# sm7_redraw.net
KiCad netlist of a schematic drawn in EAGLE
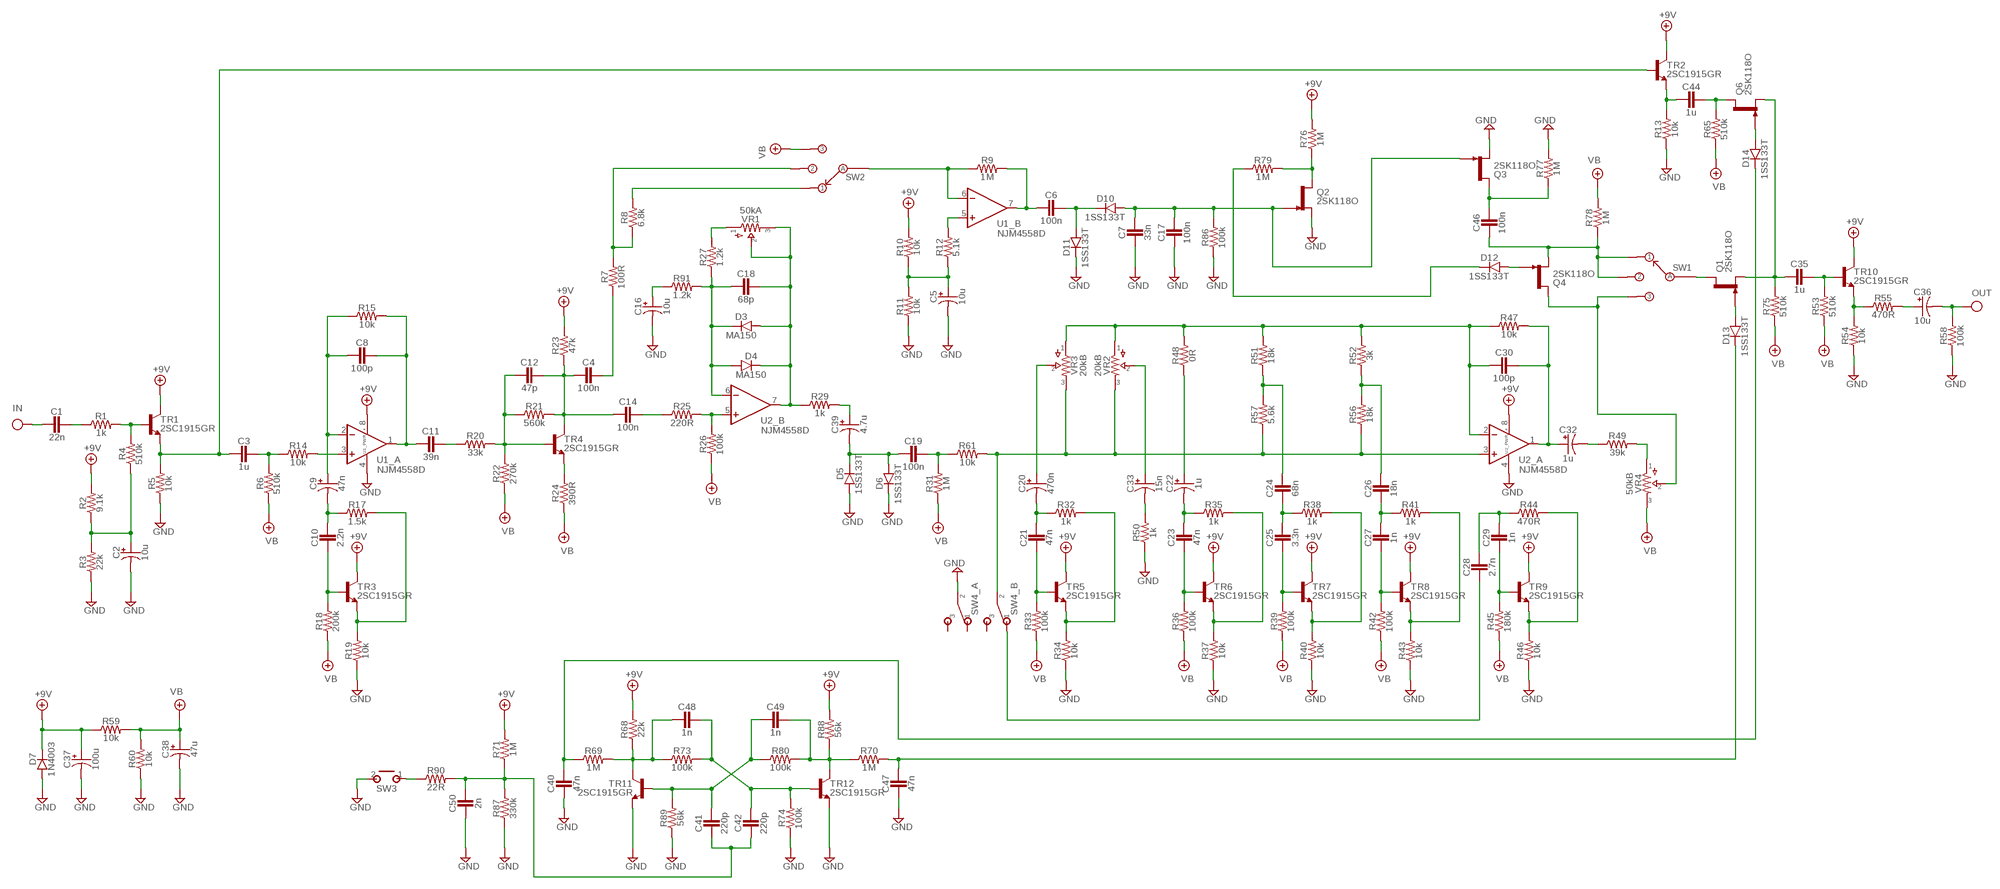
[diagram p0: schematic, sheet 1]

(export (version "E")
  (design (tool "Eeschema 10.0.6"))
  (components
    (comp (ref "C1")
      (value "22n")
      (footprint "eagle-import:BOX_SMALL")
      (libsource (lib "eagle-import") (part "CER/FILMBOX.1"))
    )
    (comp (ref "C2")
      (value "10u")
      (footprint "eagle-import:040_020")
      (libsource (lib "eagle-import") (part "0400"))
    )
    (comp (ref "C3")
      (value "1u")
      (footprint "eagle-import:BOX_SMALL")
      (libsource (lib "eagle-import") (part "CER/FILMBOX.1"))
    )
    (comp (ref "C4")
      (value "100n")
      (footprint "eagle-import:BOX_SMALL")
      (libsource (lib "eagle-import") (part "CER/FILMBOX.1"))
    )
    (comp (ref "C5")
      (value "10u")
      (footprint "eagle-import:040_020")
      (libsource (lib "eagle-import") (part "0400"))
    )
    (comp (ref "C6")
      (value "100n")
      (footprint "eagle-import:BOX_SMALL")
      (libsource (lib "eagle-import") (part "CER/FILMBOX.1"))
    )
    (comp (ref "C7")
      (value "33n")
      (footprint "eagle-import:BOX_SMALL")
      (libsource (lib "eagle-import") (part "CER/FILMBOX.1"))
    )
    (comp (ref "C8")
      (value "100p")
      (footprint "eagle-import:BOX_SMALL")
      (libsource (lib "eagle-import") (part "CER/FILMBOX.1"))
    )
    (comp (ref "C9")
      (value "47n")
      (footprint "eagle-import:040_020")
      (libsource (lib "eagle-import") (part "0400"))
    )
    (comp (ref "C10")
      (value "2.2n")
      (footprint "eagle-import:BOX_SMALL")
      (libsource (lib "eagle-import") (part "CER/FILMBOX.1"))
    )
    (comp (ref "C11")
      (value "39n")
      (footprint "eagle-import:BOX_SMALL")
      (libsource (lib "eagle-import") (part "CER/FILMBOX.1"))
    )
    (comp (ref "C12")
      (value "47p")
      (footprint "eagle-import:BOX_SMALL")
      (libsource (lib "eagle-import") (part "CER/FILMBOX.1"))
    )
    (comp (ref "C14")
      (value "100n")
      (footprint "eagle-import:BOX_SMALL")
      (libsource (lib "eagle-import") (part "CER/FILMBOX.1"))
    )
    (comp (ref "C16")
      (value "10u")
      (footprint "eagle-import:040_020")
      (libsource (lib "eagle-import") (part "0400"))
    )
    (comp (ref "C17")
      (value "100n")
      (footprint "eagle-import:BOX_SMALL")
      (libsource (lib "eagle-import") (part "CER/FILMBOX.1"))
    )
    (comp (ref "C18")
      (value "68p")
      (footprint "eagle-import:BOX_SMALL")
      (libsource (lib "eagle-import") (part "CER/FILMBOX.1"))
    )
    (comp (ref "C19")
      (value "100n")
      (footprint "eagle-import:BOX_SMALL")
      (libsource (lib "eagle-import") (part "CER/FILMBOX.1"))
    )
    (comp (ref "C20")
      (value "470n")
      (footprint "eagle-import:040_020")
      (libsource (lib "eagle-import") (part "0400"))
    )
    (comp (ref "C21")
      (value "47n")
      (footprint "eagle-import:BOX_SMALL")
      (libsource (lib "eagle-import") (part "CER/FILMBOX.1"))
    )
    (comp (ref "C22")
      (value "1u")
      (footprint "eagle-import:040_020")
      (libsource (lib "eagle-import") (part "0400"))
    )
    (comp (ref "C23")
      (value "47n")
      (footprint "eagle-import:BOX_SMALL")
      (libsource (lib "eagle-import") (part "CER/FILMBOX.1"))
    )
    (comp (ref "C24")
      (value "68n")
      (footprint "eagle-import:BOX_SMALL")
      (libsource (lib "eagle-import") (part "CER/FILMBOX.1"))
    )
    (comp (ref "C25")
      (value "3.3n")
      (footprint "eagle-import:BOX_SMALL")
      (libsource (lib "eagle-import") (part "CER/FILMBOX.1"))
    )
    (comp (ref "C26")
      (value "18n")
      (footprint "eagle-import:BOX_SMALL")
      (libsource (lib "eagle-import") (part "CER/FILMBOX.1"))
    )
    (comp (ref "C27")
      (value "1n")
      (footprint "eagle-import:BOX_SMALL")
      (libsource (lib "eagle-import") (part "CER/FILMBOX.1"))
    )
    (comp (ref "C28")
      (value "2.7n")
      (footprint "eagle-import:BOX_SMALL")
      (libsource (lib "eagle-import") (part "CER/FILMBOX.1"))
    )
    (comp (ref "C29")
      (value "1n")
      (footprint "eagle-import:BOX_SMALL")
      (libsource (lib "eagle-import") (part "CER/FILMBOX.1"))
    )
    (comp (ref "C30")
      (value "100p")
      (footprint "eagle-import:BOX_SMALL")
      (libsource (lib "eagle-import") (part "CER/FILMBOX.1"))
    )
    (comp (ref "C32")
      (value "1u")
      (footprint "eagle-import:040_020")
      (libsource (lib "eagle-import") (part "0400"))
    )
    (comp (ref "C33")
      (value "15n")
      (footprint "eagle-import:040_020")
      (libsource (lib "eagle-import") (part "0400"))
    )
    (comp (ref "C35")
      (value "1u")
      (footprint "eagle-import:BOX_SMALL")
      (libsource (lib "eagle-import") (part "CER/FILMBOX.1"))
    )
    (comp (ref "C36")
      (value "10u")
      (footprint "eagle-import:040_020")
      (libsource (lib "eagle-import") (part "0400"))
    )
    (comp (ref "C37")
      (value "100u")
      (footprint "eagle-import:040_020")
      (libsource (lib "eagle-import") (part "0400"))
    )
    (comp (ref "C38")
      (value "47u")
      (footprint "eagle-import:040_020")
      (libsource (lib "eagle-import") (part "0400"))
    )
    (comp (ref "C39")
      (value "4.7u")
      (footprint "eagle-import:040_020")
      (libsource (lib "eagle-import") (part "0400"))
    )
    (comp (ref "C40")
      (value "47n")
      (footprint "eagle-import:BOX_SMALL")
      (libsource (lib "eagle-import") (part "CER/FILMBOX.1"))
    )
    (comp (ref "C41")
      (value "220p")
      (footprint "eagle-import:BOX_SMALL")
      (libsource (lib "eagle-import") (part "CER/FILMBOX.1"))
    )
    (comp (ref "C42")
      (value "220p")
      (footprint "eagle-import:BOX_SMALL")
      (libsource (lib "eagle-import") (part "CER/FILMBOX.1"))
    )
    (comp (ref "C44")
      (value "1u")
      (footprint "eagle-import:BOX_SMALL")
      (libsource (lib "eagle-import") (part "CER/FILMBOX.1"))
    )
    (comp (ref "C46")
      (value "100n")
      (footprint "eagle-import:BOX_SMALL")
      (libsource (lib "eagle-import") (part "CER/FILMBOX.1"))
    )
    (comp (ref "C47")
      (value "47n")
      (footprint "eagle-import:BOX_SMALL")
      (libsource (lib "eagle-import") (part "CER/FILMBOX.1"))
    )
    (comp (ref "C48")
      (value "1n")
      (footprint "eagle-import:BOX_SMALL")
      (libsource (lib "eagle-import") (part "CER/FILMBOX.1"))
    )
    (comp (ref "C49")
      (value "1n")
      (footprint "eagle-import:BOX_SMALL")
      (libsource (lib "eagle-import") (part "CER/FILMBOX.1"))
    )
    (comp (ref "C50")
      (value "2n")
      (footprint "eagle-import:BOX_SMALL")
      (libsource (lib "eagle-import") (part "CER/FILMBOX.1"))
    )
    (comp (ref "D3")
      (value "MA150")
      (footprint "eagle-import:DO41-2")
      (libsource (lib "eagle-import") (part "DO41.2"))
    )
    (comp (ref "D4")
      (value "MA150")
      (footprint "eagle-import:DO41-2")
      (libsource (lib "eagle-import") (part "DO41.2"))
    )
    (comp (ref "D5")
      (value "1SS133T")
      (footprint "eagle-import:DO41-2")
      (libsource (lib "eagle-import") (part "DO41.2"))
    )
    (comp (ref "D6")
      (value "1SS133T")
      (footprint "eagle-import:DO41-2")
      (libsource (lib "eagle-import") (part "DO41.2"))
    )
    (comp (ref "D7")
      (value "1N4003")
      (footprint "eagle-import:DO41-2")
      (libsource (lib "eagle-import") (part "DO41.2"))
    )
    (comp (ref "D10")
      (value "1SS133T")
      (footprint "eagle-import:DO41-2")
      (libsource (lib "eagle-import") (part "DO41.2"))
    )
    (comp (ref "D11")
      (value "1SS133T")
      (footprint "eagle-import:DO41-2")
      (libsource (lib "eagle-import") (part "DO41.2"))
    )
    (comp (ref "D12")
      (value "1SS133T")
      (footprint "eagle-import:DO41-2")
      (libsource (lib "eagle-import") (part "DO41.2"))
    )
    (comp (ref "D13")
      (value "1SS133T")
      (footprint "eagle-import:DO41-2")
      (libsource (lib "eagle-import") (part "DO41.2"))
    )
    (comp (ref "D14")
      (value "1SS133T")
      (footprint "eagle-import:DO41-2")
      (libsource (lib "eagle-import") (part "DO41.2"))
    )
    (comp (ref "Q1")
      (value "2SK118O")
      (footprint "eagle-import:TO92-")
      (libsource (lib "eagle-import") (part "2N5457"))
    )
    (comp (ref "Q2")
      (value "2SK118O")
      (footprint "eagle-import:TO92-")
      (libsource (lib "eagle-import") (part "2N5457"))
    )
    (comp (ref "Q3")
      (value "2SK118O")
      (footprint "eagle-import:TO92-")
      (libsource (lib "eagle-import") (part "2N5457"))
    )
    (comp (ref "Q4")
      (value "2SK118O")
      (footprint "eagle-import:TO92-")
      (libsource (lib "eagle-import") (part "2N5457"))
    )
    (comp (ref "Q6")
      (value "2SK118O")
      (footprint "eagle-import:TO92-")
      (libsource (lib "eagle-import") (part "2N5457"))
    )
    (comp (ref "R1")
      (value "1k")
      (footprint "eagle-import:R0207_3")
      (libsource (lib "eagle-import") (part "R_.3B"))
    )
    (comp (ref "R2")
      (value "9.1k")
      (footprint "eagle-import:R0207_3")
      (libsource (lib "eagle-import") (part "R_.3B"))
    )
    (comp (ref "R3")
      (value "22k")
      (footprint "eagle-import:R0207_3")
      (libsource (lib "eagle-import") (part "R_.3B"))
    )
    (comp (ref "R4")
      (value "510k")
      (footprint "eagle-import:R0207_3")
      (libsource (lib "eagle-import") (part "R_.3B"))
    )
    (comp (ref "R5")
      (value "10k")
      (footprint "eagle-import:R0207_3")
      (libsource (lib "eagle-import") (part "R_.3B"))
    )
    (comp (ref "R6")
      (value "510k")
      (footprint "eagle-import:R0207_3")
      (libsource (lib "eagle-import") (part "R_.3B"))
    )
    (comp (ref "R7")
      (value "100R")
      (footprint "eagle-import:R0207_3")
      (libsource (lib "eagle-import") (part "R_.3B"))
    )
    (comp (ref "R8")
      (value "6.8k")
      (footprint "eagle-import:R0207_3")
      (libsource (lib "eagle-import") (part "R_.3B"))
    )
    (comp (ref "R9")
      (value "1M")
      (footprint "eagle-import:R0207_3")
      (libsource (lib "eagle-import") (part "R_.3B"))
    )
    (comp (ref "R10")
      (value "10k")
      (footprint "eagle-import:R0207_3")
      (libsource (lib "eagle-import") (part "R_.3B"))
    )
    (comp (ref "R11")
      (value "10k")
      (footprint "eagle-import:R0207_3")
      (libsource (lib "eagle-import") (part "R_.3B"))
    )
    (comp (ref "R12")
      (value "5.1k")
      (footprint "eagle-import:R0207_3")
      (libsource (lib "eagle-import") (part "R_.3B"))
    )
    (comp (ref "R13")
      (value "10k")
      (footprint "eagle-import:R0207_3")
      (libsource (lib "eagle-import") (part "R_.3B"))
    )
    (comp (ref "R14")
      (value "10k")
      (footprint "eagle-import:R0207_3")
      (libsource (lib "eagle-import") (part "R_.3B"))
    )
    (comp (ref "R15")
      (value "10k")
      (footprint "eagle-import:R0207_3")
      (libsource (lib "eagle-import") (part "R_.3B"))
    )
    (comp (ref "R17")
      (value "1.5k")
      (footprint "eagle-import:R0207_3")
      (libsource (lib "eagle-import") (part "R_.3B"))
    )
    (comp (ref "R18")
      (value "200k")
      (footprint "eagle-import:R0207_3")
      (libsource (lib "eagle-import") (part "R_.3B"))
    )
    (comp (ref "R19")
      (value "10k")
      (footprint "eagle-import:R0207_3")
      (libsource (lib "eagle-import") (part "R_.3B"))
    )
    (comp (ref "R20")
      (value "33k")
      (footprint "eagle-import:R0207_3")
      (libsource (lib "eagle-import") (part "R_.3B"))
    )
    (comp (ref "R21")
      (value "560k")
      (footprint "eagle-import:R0207_3")
      (libsource (lib "eagle-import") (part "R_.3B"))
    )
    (comp (ref "R22")
      (value "270k")
      (footprint "eagle-import:R0207_3")
      (libsource (lib "eagle-import") (part "R_.3B"))
    )
    (comp (ref "R23")
      (value "47k")
      (footprint "eagle-import:R0207_3")
      (libsource (lib "eagle-import") (part "R_.3B"))
    )
    (comp (ref "R24")
      (value "390R")
      (footprint "eagle-import:R0207_3")
      (libsource (lib "eagle-import") (part "R_.3B"))
    )
    (comp (ref "R25")
      (value "220R")
      (footprint "eagle-import:R0207_3")
      (libsource (lib "eagle-import") (part "R_.3B"))
    )
    (comp (ref "R26")
      (value "100k")
      (footprint "eagle-import:R0207_3")
      (libsource (lib "eagle-import") (part "R_.3B"))
    )
    (comp (ref "R27")
      (value "1.2k")
      (footprint "eagle-import:R0207_3")
      (libsource (lib "eagle-import") (part "R_.3B"))
    )
    (comp (ref "R29")
      (value "1k")
      (footprint "eagle-import:R0207_3")
      (libsource (lib "eagle-import") (part "R_.3B"))
    )
    (comp (ref "R31")
      (value "1M")
      (footprint "eagle-import:R0207_3")
      (libsource (lib "eagle-import") (part "R_.3B"))
    )
    (comp (ref "R32")
      (value "1k")
      (footprint "eagle-import:R0207_3")
      (libsource (lib "eagle-import") (part "R_.3B"))
    )
    (comp (ref "R33")
      (value "100k")
      (footprint "eagle-import:R0207_3")
      (libsource (lib "eagle-import") (part "R_.3B"))
    )
    (comp (ref "R34")
      (value "10k")
      (footprint "eagle-import:R0207_3")
      (libsource (lib "eagle-import") (part "R_.3B"))
    )
    (comp (ref "R35")
      (value "1k")
      (footprint "eagle-import:R0207_3")
      (libsource (lib "eagle-import") (part "R_.3B"))
    )
    (comp (ref "R36")
      (value "100k")
      (footprint "eagle-import:R0207_3")
      (libsource (lib "eagle-import") (part "R_.3B"))
    )
    (comp (ref "R37")
      (value "10k")
      (footprint "eagle-import:R0207_3")
      (libsource (lib "eagle-import") (part "R_.3B"))
    )
    (comp (ref "R38")
      (value "1k")
      (footprint "eagle-import:R0207_3")
      (libsource (lib "eagle-import") (part "R_.3B"))
    )
    (comp (ref "R39")
      (value "100k")
      (footprint "eagle-import:R0207_3")
      (libsource (lib "eagle-import") (part "R_.3B"))
    )
    (comp (ref "R40")
      (value "10k")
      (footprint "eagle-import:R0207_3")
      (libsource (lib "eagle-import") (part "R_.3B"))
    )
    (comp (ref "R41")
      (value "1k")
      (footprint "eagle-import:R0207_3")
      (libsource (lib "eagle-import") (part "R_.3B"))
    )
    (comp (ref "R42")
      (value "100k")
      (footprint "eagle-import:R0207_3")
      (libsource (lib "eagle-import") (part "R_.3B"))
    )
    (comp (ref "R43")
      (value "10k")
      (footprint "eagle-import:R0207_3")
      (libsource (lib "eagle-import") (part "R_.3B"))
    )
    (comp (ref "R44")
      (value "470R")
      (footprint "eagle-import:R0207_3")
      (libsource (lib "eagle-import") (part "R_.3B"))
    )
    (comp (ref "R45")
      (value "180k")
      (footprint "eagle-import:R0207_3")
      (libsource (lib "eagle-import") (part "R_.3B"))
    )
    (comp (ref "R46")
      (value "10k")
      (footprint "eagle-import:R0207_3")
      (libsource (lib "eagle-import") (part "R_.3B"))
    )
    (comp (ref "R47")
      (value "10k")
      (footprint "eagle-import:R0207_3")
      (libsource (lib "eagle-import") (part "R_.3B"))
    )
    (comp (ref "R48")
      (value "0R")
      (footprint "eagle-import:R0207_3")
      (libsource (lib "eagle-import") (part "R_.3B"))
    )
    (comp (ref "R49")
      (value "39k")
      (footprint "eagle-import:R0207_3")
      (libsource (lib "eagle-import") (part "R_.3B"))
    )
    (comp (ref "R50")
      (value "1k")
      (footprint "eagle-import:R0207_3")
      (libsource (lib "eagle-import") (part "R_.3B"))
    )
    (comp (ref "R51")
      (value "18k")
      (footprint "eagle-import:R0207_3")
      (libsource (lib "eagle-import") (part "R_.3B"))
    )
    (comp (ref "R52")
      (value "3k")
      (footprint "eagle-import:R0207_3")
      (libsource (lib "eagle-import") (part "R_.3B"))
    )
    (comp (ref "R53")
      (value "510k")
      (footprint "eagle-import:R0207_3")
      (libsource (lib "eagle-import") (part "R_.3B"))
    )
    (comp (ref "R54")
      (value "10k")
      (footprint "eagle-import:R0207_3")
      (libsource (lib "eagle-import") (part "R_.3B"))
    )
    (comp (ref "R55")
      (value "470R")
      (footprint "eagle-import:R0207_3")
      (libsource (lib "eagle-import") (part "R_.3B"))
    )
    (comp (ref "R56")
      (value "18k")
      (footprint "eagle-import:R0207_3")
      (libsource (lib "eagle-import") (part "R_.3B"))
    )
    (comp (ref "R57")
      (value "5.6k")
      (footprint "eagle-import:R0207_3")
      (libsource (lib "eagle-import") (part "R_.3B"))
    )
    (comp (ref "R58")
      (value "100k")
      (footprint "eagle-import:R0207_3")
      (libsource (lib "eagle-import") (part "R_.3B"))
    )
    (comp (ref "R59")
      (value "10k")
      (footprint "eagle-import:R0207_3")
      (libsource (lib "eagle-import") (part "R_.3B"))
    )
    (comp (ref "R60")
      (value "10k")
      (footprint "eagle-import:R0207_3")
      (libsource (lib "eagle-import") (part "R_.3B"))
    )
    (comp (ref "R61")
      (value "10k")
      (footprint "eagle-import:R0207_3")
      (libsource (lib "eagle-import") (part "R_.3B"))
    )
    (comp (ref "R65")
      (value "510k")
      (footprint "eagle-import:R0207_3")
      (libsource (lib "eagle-import") (part "R_.3B"))
    )
    (comp (ref "R68")
      (value "22k")
      (footprint "eagle-import:R0207_3")
      (libsource (lib "eagle-import") (part "R_.3B"))
    )
    (comp (ref "R69")
      (value "1M")
      (footprint "eagle-import:R0207_3")
      (libsource (lib "eagle-import") (part "R_.3B"))
    )
    (comp (ref "R70")
      (value "1M")
      (footprint "eagle-import:R0207_3")
      (libsource (lib "eagle-import") (part "R_.3B"))
    )
    (comp (ref "R71")
      (value "1M")
      (footprint "eagle-import:R0207_3")
      (libsource (lib "eagle-import") (part "R_.3B"))
    )
    (comp (ref "R73")
      (value "100k")
      (footprint "eagle-import:R0207_3")
      (libsource (lib "eagle-import") (part "R_.3B"))
    )
    (comp (ref "R74")
      (value "100k")
      (footprint "eagle-import:R0207_3")
      (libsource (lib "eagle-import") (part "R_.3B"))
    )
    (comp (ref "R75")
      (value "510k")
      (footprint "eagle-import:R0207_3")
      (libsource (lib "eagle-import") (part "R_.3B"))
    )
    (comp (ref "R76")
      (value "1M")
      (footprint "eagle-import:R0207_3")
      (libsource (lib "eagle-import") (part "R_.3B"))
    )
    (comp (ref "R77")
      (value "1M")
      (footprint "eagle-import:R0207_3")
      (libsource (lib "eagle-import") (part "R_.3B"))
    )
    (comp (ref "R78")
      (value "1M")
      (footprint "eagle-import:R0207_3")
      (libsource (lib "eagle-import") (part "R_.3B"))
    )
    (comp (ref "R79")
      (value "1M")
      (footprint "eagle-import:R0207_3")
      (libsource (lib "eagle-import") (part "R_.3B"))
    )
    (comp (ref "R80")
      (value "100k")
      (footprint "eagle-import:R0207_3")
      (libsource (lib "eagle-import") (part "R_.3B"))
    )
    (comp (ref "R86")
      (value "100k")
      (footprint "eagle-import:R0207_3")
      (libsource (lib "eagle-import") (part "R_.3B"))
    )
    (comp (ref "R87")
      (value "330k")
      (footprint "eagle-import:R0207_3")
      (libsource (lib "eagle-import") (part "R_.3B"))
    )
    (comp (ref "R88")
      (value "56k")
      (footprint "eagle-import:R0207_3")
      (libsource (lib "eagle-import") (part "R_.3B"))
    )
    (comp (ref "R89")
      (value "56k")
      (footprint "eagle-import:R0207_3")
      (libsource (lib "eagle-import") (part "R_.3B"))
    )
    (comp (ref "R90")
      (value "22R")
      (footprint "eagle-import:R0207_3")
      (libsource (lib "eagle-import") (part "R_.3B"))
    )
    (comp (ref "R91")
      (value "1.2k")
      (footprint "eagle-import:R0207_3")
      (libsource (lib "eagle-import") (part "R_.3B"))
    )
    (comp (ref "SW1")
      (value "1P3T")
      (footprint "eagle-import:1P3T")
      (libsource (lib "eagle-import") (part "1P3T"))
    )
    (comp (ref "SW2")
      (value "1P3T")
      (footprint "eagle-import:1P3T")
      (libsource (lib "eagle-import") (part "1P3T"))
    )
    (comp (ref "SW3")
      (value "MOMENTARY")
      (footprint "eagle-import:SPST")
      (libsource (lib "eagle-import") (part "MOMENTARY"))
    )
    (comp (ref "SW4")
      (value "DPDT")
      (footprint "eagle-import:DPDT")
      (libsource (lib "eagle-import") (part "DPDT"))
    )
    (comp (ref "TR1")
      (value "2SC1915GR")
      (footprint "eagle-import:TO92-")
      (libsource (lib "eagle-import") (part "2SC828A"))
    )
    (comp (ref "TR2")
      (value "2SC1915GR")
      (footprint "eagle-import:TO92-")
      (libsource (lib "eagle-import") (part "2SC828A"))
    )
    (comp (ref "TR3")
      (value "2SC1915GR")
      (footprint "eagle-import:TO92-")
      (libsource (lib "eagle-import") (part "2SC828A"))
    )
    (comp (ref "TR4")
      (value "2SC1915GR")
      (footprint "eagle-import:TO92-")
      (libsource (lib "eagle-import") (part "2SC828A"))
    )
    (comp (ref "TR5")
      (value "2SC1915GR")
      (footprint "eagle-import:TO92-")
      (libsource (lib "eagle-import") (part "2SC828A"))
    )
    (comp (ref "TR6")
      (value "2SC1915GR")
      (footprint "eagle-import:TO92-")
      (libsource (lib "eagle-import") (part "2SC828A"))
    )
    (comp (ref "TR7")
      (value "2SC1915GR")
      (footprint "eagle-import:TO92-")
      (libsource (lib "eagle-import") (part "2SC828A"))
    )
    (comp (ref "TR8")
      (value "2SC1915GR")
      (footprint "eagle-import:TO92-")
      (libsource (lib "eagle-import") (part "2SC828A"))
    )
    (comp (ref "TR9")
      (value "2SC1915GR")
      (footprint "eagle-import:TO92-")
      (libsource (lib "eagle-import") (part "2SC828A"))
    )
    (comp (ref "TR10")
      (value "2SC1915GR")
      (footprint "eagle-import:TO92-")
      (libsource (lib "eagle-import") (part "2SC828A"))
    )
    (comp (ref "TR11")
      (value "2SC1915GR")
      (footprint "eagle-import:TO92-")
      (libsource (lib "eagle-import") (part "2SC828A"))
    )
    (comp (ref "TR12")
      (value "2SC1915GR")
      (footprint "eagle-import:TO92-")
      (libsource (lib "eagle-import") (part "2SC828A"))
    )
    (comp (ref "U1")
      (value "NJM4558D")
      (footprint "eagle-import:DIL0")
      (libsource (lib "eagle-import") (part "DUALTH"))
    )
    (comp (ref "U2")
      (value "NJM4558D")
      (footprint "eagle-import:DIL0")
      (libsource (lib "eagle-import") (part "DUALTH"))
    )
    (comp (ref "VR1")
      (value "50kA")
      (footprint "eagle-import:16MM")
      (libsource (lib "eagle-import") (part "POTS16MM"))
    )
    (comp (ref "VR2")
      (value "20kB")
      (footprint "eagle-import:16MM")
      (libsource (lib "eagle-import") (part "POTS16MM"))
    )
    (comp (ref "VR3")
      (value "20kB")
      (footprint "eagle-import:16MM")
      (libsource (lib "eagle-import") (part "POTS16MM"))
    )
    (comp (ref "VR4")
      (value "50kB")
      (footprint "eagle-import:16MM")
      (libsource (lib "eagle-import") (part "POTS16MM"))
    )
  )
  (nets
    (net (code "1") (name "+9V") (class "Default")
      (node (ref "C37") (pin "+") (pinfunction "+_+") (pintype "passive"))
      (node (ref "D7") (pin "C") (pinfunction "C_C") (pintype "passive"))
      (node (ref "R10") (pin "2") (pinfunction "2_2") (pintype "passive"))
      (node (ref "R2") (pin "2") (pinfunction "2_2") (pintype "passive"))
      (node (ref "R23") (pin "2") (pinfunction "2_2") (pintype "passive"))
      (node (ref "R59") (pin "1") (pinfunction "1_1") (pintype "passive"))
      (node (ref "R68") (pin "2") (pinfunction "2_2") (pintype "passive"))
      (node (ref "R71") (pin "2") (pinfunction "2_2") (pintype "passive"))
      (node (ref "R76") (pin "2") (pinfunction "2_2") (pintype "passive"))
      (node (ref "R88") (pin "2") (pinfunction "2_2") (pintype "passive"))
      (node (ref "TR1") (pin "2") (pinfunction "C_2") (pintype "passive"))
      (node (ref "TR10") (pin "2") (pinfunction "C_2") (pintype "passive"))
      (node (ref "TR2") (pin "2") (pinfunction "C_2") (pintype "passive"))
      (node (ref "TR3") (pin "2") (pinfunction "C_2") (pintype "passive"))
      (node (ref "TR5") (pin "2") (pinfunction "C_2") (pintype "passive"))
      (node (ref "TR6") (pin "2") (pinfunction "C_2") (pintype "passive"))
      (node (ref "TR7") (pin "2") (pinfunction "C_2") (pintype "passive"))
      (node (ref "TR8") (pin "2") (pinfunction "C_2") (pintype "passive"))
      (node (ref "TR9") (pin "2") (pinfunction "C_2") (pintype "passive"))
      (node (ref "U1") (pin "8") (pinfunction "V+_8") (pintype "power_in"))
      (node (ref "U2") (pin "8") (pinfunction "V+_8") (pintype "power_in"))
    )
    (net (code "2") (name "GND") (class "Default")
      (node (ref "C16") (pin "-") (pinfunction "-_-") (pintype "passive"))
      (node (ref "C17") (pin "2") (pinfunction "2_2") (pintype "passive"))
      (node (ref "C2") (pin "-") (pinfunction "-_-") (pintype "passive"))
      (node (ref "C37") (pin "-") (pinfunction "-_-") (pintype "passive"))
      (node (ref "C38") (pin "-") (pinfunction "-_-") (pintype "passive"))
      (node (ref "C40") (pin "2") (pinfunction "2_2") (pintype "passive"))
      (node (ref "C47") (pin "2") (pinfunction "2_2") (pintype "passive"))
      (node (ref "C5") (pin "-") (pinfunction "-_-") (pintype "passive"))
      (node (ref "C50") (pin "2") (pinfunction "2_2") (pintype "passive"))
      (node (ref "C7") (pin "2") (pinfunction "2_2") (pintype "passive"))
      (node (ref "D11") (pin "C") (pinfunction "C_C") (pintype "passive"))
      (node (ref "D5") (pin "A") (pinfunction "A_A") (pintype "passive"))
      (node (ref "D6") (pin "C") (pinfunction "C_C") (pintype "passive"))
      (node (ref "D7") (pin "A") (pinfunction "A_A") (pintype "passive"))
      (node (ref "Q2") (pin "2") (pinfunction "S_2") (pintype "passive"))
      (node (ref "Q3") (pin "2") (pinfunction "S_2") (pintype "passive"))
      (node (ref "R11") (pin "1") (pinfunction "1_1") (pintype "passive"))
      (node (ref "R13") (pin "1") (pinfunction "1_1") (pintype "passive"))
      (node (ref "R19") (pin "1") (pinfunction "1_1") (pintype "passive"))
      (node (ref "R3") (pin "1") (pinfunction "1_1") (pintype "passive"))
      (node (ref "R34") (pin "1") (pinfunction "1_1") (pintype "passive"))
      (node (ref "R37") (pin "1") (pinfunction "1_1") (pintype "passive"))
      (node (ref "R40") (pin "1") (pinfunction "1_1") (pintype "passive"))
      (node (ref "R43") (pin "1") (pinfunction "1_1") (pintype "passive"))
      (node (ref "R46") (pin "1") (pinfunction "1_1") (pintype "passive"))
      (node (ref "R5") (pin "1") (pinfunction "1_1") (pintype "passive"))
      (node (ref "R50") (pin "1") (pinfunction "1_1") (pintype "passive"))
      (node (ref "R54") (pin "1") (pinfunction "1_1") (pintype "passive"))
      (node (ref "R58") (pin "1") (pinfunction "1_1") (pintype "passive"))
      (node (ref "R60") (pin "1") (pinfunction "1_1") (pintype "passive"))
      (node (ref "R74") (pin "1") (pinfunction "1_1") (pintype "passive"))
      (node (ref "R77") (pin "2") (pinfunction "2_2") (pintype "passive"))
      (node (ref "R86") (pin "1") (pinfunction "1_1") (pintype "passive"))
      (node (ref "R87") (pin "1") (pinfunction "1_1") (pintype "passive"))
      (node (ref "R89") (pin "1") (pinfunction "1_1") (pintype "passive"))
      (node (ref "SW3") (pin "2") (pinfunction "S_2") (pintype "passive"))
      (node (ref "SW4") (pin "A2") (pinfunction "2_A2") (pintype "passive"))
      (node (ref "TR11") (pin "3") (pinfunction "E_3") (pintype "passive"))
      (node (ref "TR12") (pin "3") (pinfunction "E_3") (pintype "passive"))
      (node (ref "U1") (pin "4") (pinfunction "V-_4") (pintype "power_in"))
      (node (ref "U2") (pin "4") (pinfunction "V-_4") (pintype "power_in"))
    )
    (net (code "3") (name "IN") (class "Default")
      (node (ref "C1") (pin "2") (pinfunction "2_2") (pintype "passive"))
    )
    (net (code "4") (name "Net-(C1-Pad1)") (class "Default")
      (node (ref "C1") (pin "1") (pinfunction "1_1") (pintype "passive"))
      (node (ref "R1") (pin "1") (pinfunction "1_1") (pintype "passive"))
    )
    (net (code "5") (name "Net-(C2-Pad+)") (class "Default")
      (node (ref "C2") (pin "+") (pinfunction "+_+") (pintype "passive"))
      (node (ref "R2") (pin "1") (pinfunction "1_1") (pintype "passive"))
      (node (ref "R3") (pin "2") (pinfunction "2_2") (pintype "passive"))
      (node (ref "R4") (pin "1") (pinfunction "1_1") (pintype "passive"))
    )
    (net (code "6") (name "Net-(C3-Pad1)") (class "Default")
      (node (ref "C3") (pin "1") (pinfunction "1_1") (pintype "passive"))
      (node (ref "R14") (pin "1") (pinfunction "1_1") (pintype "passive"))
      (node (ref "R6") (pin "2") (pinfunction "2_2") (pintype "passive"))
    )
    (net (code "7") (name "Net-(C4-Pad1)") (class "Default")
      (node (ref "C4") (pin "1") (pinfunction "1_1") (pintype "passive"))
      (node (ref "R7") (pin "1") (pinfunction "1_1") (pintype "passive"))
    )
    (net (code "8") (name "Net-(C5-Pad+)") (class "Default")
      (node (ref "C5") (pin "+") (pinfunction "+_+") (pintype "passive"))
      (node (ref "R10") (pin "1") (pinfunction "1_1") (pintype "passive"))
      (node (ref "R11") (pin "2") (pinfunction "2_2") (pintype "passive"))
      (node (ref "R12") (pin "1") (pinfunction "1_1") (pintype "passive"))
    )
    (net (code "9") (name "Net-(C6-Pad1)") (class "Default")
      (node (ref "C6") (pin "1") (pinfunction "1_1") (pintype "passive"))
      (node (ref "D10") (pin "C") (pinfunction "C_C") (pintype "passive"))
      (node (ref "D11") (pin "A") (pinfunction "A_A") (pintype "passive"))
    )
    (net (code "10") (name "Net-(C10-Pad1)") (class "Default")
      (node (ref "C10") (pin "1") (pinfunction "1_1") (pintype "passive"))
      (node (ref "C9") (pin "-") (pinfunction "-_-") (pintype "passive"))
      (node (ref "R17") (pin "1") (pinfunction "1_1") (pintype "passive"))
    )
    (net (code "11") (name "Net-(C11-Pad1)") (class "Default")
      (node (ref "C11") (pin "1") (pinfunction "1_1") (pintype "passive"))
      (node (ref "R20") (pin "1") (pinfunction "1_1") (pintype "passive"))
    )
    (net (code "12") (name "Net-(C14-Pad1)") (class "Default")
      (node (ref "C14") (pin "1") (pinfunction "1_1") (pintype "passive"))
      (node (ref "R25") (pin "1") (pinfunction "1_1") (pintype "passive"))
    )
    (net (code "13") (name "Net-(C16-Pad+)") (class "Default")
      (node (ref "C16") (pin "+") (pinfunction "+_+") (pintype "passive"))
      (node (ref "R91") (pin "1") (pinfunction "1_1") (pintype "passive"))
    )
    (net (code "14") (name "Net-(C19-Pad1)") (class "Default")
      (node (ref "C19") (pin "1") (pinfunction "1_1") (pintype "passive"))
      (node (ref "R31") (pin "2") (pinfunction "2_2") (pintype "passive"))
      (node (ref "R61") (pin "1") (pinfunction "1_1") (pintype "passive"))
    )
    (net (code "15") (name "Net-(C19-Pad2)") (class "Default")
      (node (ref "C19") (pin "2") (pinfunction "2_2") (pintype "passive"))
      (node (ref "C39") (pin "-") (pinfunction "-_-") (pintype "passive"))
      (node (ref "D5") (pin "C") (pinfunction "C_C") (pintype "passive"))
      (node (ref "D6") (pin "A") (pinfunction "A_A") (pintype "passive"))
    )
    (net (code "16") (name "Net-(C20-Pad+)") (class "Default")
      (node (ref "C20") (pin "+") (pinfunction "+_+") (pintype "passive"))
      (node (ref "VR3") (pin "2") (pinfunction "2_2") (pintype "passive"))
    )
    (net (code "17") (name "Net-(C20-Pad-)") (class "Default")
      (node (ref "C20") (pin "-") (pinfunction "-_-") (pintype "passive"))
      (node (ref "C21") (pin "1") (pinfunction "1_1") (pintype "passive"))
      (node (ref "R32") (pin "1") (pinfunction "1_1") (pintype "passive"))
    )
    (net (code "18") (name "Net-(C22-Pad+)") (class "Default")
      (node (ref "C22") (pin "+") (pinfunction "+_+") (pintype "passive"))
      (node (ref "R48") (pin "1") (pinfunction "1_1") (pintype "passive"))
    )
    (net (code "19") (name "Net-(C22-Pad-)") (class "Default")
      (node (ref "C22") (pin "-") (pinfunction "-_-") (pintype "passive"))
      (node (ref "C23") (pin "1") (pinfunction "1_1") (pintype "passive"))
      (node (ref "R35") (pin "1") (pinfunction "1_1") (pintype "passive"))
    )
    (net (code "20") (name "Net-(C24-Pad1)") (class "Default")
      (node (ref "C24") (pin "1") (pinfunction "1_1") (pintype "passive"))
      (node (ref "R51") (pin "1") (pinfunction "1_1") (pintype "passive"))
      (node (ref "R57") (pin "2") (pinfunction "2_2") (pintype "passive"))
    )
    (net (code "21") (name "Net-(C24-Pad2)") (class "Default")
      (node (ref "C24") (pin "2") (pinfunction "2_2") (pintype "passive"))
      (node (ref "C25") (pin "1") (pinfunction "1_1") (pintype "passive"))
      (node (ref "R38") (pin "1") (pinfunction "1_1") (pintype "passive"))
    )
    (net (code "22") (name "Net-(C26-Pad1)") (class "Default")
      (node (ref "C26") (pin "1") (pinfunction "1_1") (pintype "passive"))
      (node (ref "R52") (pin "1") (pinfunction "1_1") (pintype "passive"))
      (node (ref "R56") (pin "2") (pinfunction "2_2") (pintype "passive"))
    )
    (net (code "23") (name "Net-(C26-Pad2)") (class "Default")
      (node (ref "C26") (pin "2") (pinfunction "2_2") (pintype "passive"))
      (node (ref "C27") (pin "1") (pinfunction "1_1") (pintype "passive"))
      (node (ref "R41") (pin "1") (pinfunction "1_1") (pintype "passive"))
    )
    (net (code "24") (name "Net-(C28-Pad2)") (class "Default")
      (node (ref "C28") (pin "2") (pinfunction "2_2") (pintype "passive"))
      (node (ref "C29") (pin "1") (pinfunction "1_1") (pintype "passive"))
      (node (ref "R44") (pin "1") (pinfunction "1_1") (pintype "passive"))
    )
    (net (code "25") (name "Net-(C32-Pad-)") (class "Default")
      (node (ref "C32") (pin "-") (pinfunction "-_-") (pintype "passive"))
      (node (ref "R49") (pin "1") (pinfunction "1_1") (pintype "passive"))
    )
    (net (code "26") (name "Net-(C33-Pad+)") (class "Default")
      (node (ref "C33") (pin "+") (pinfunction "+_+") (pintype "passive"))
      (node (ref "VR2") (pin "2") (pinfunction "2_2") (pintype "passive"))
    )
    (net (code "27") (name "Net-(C33-Pad-)") (class "Default")
      (node (ref "C33") (pin "-") (pinfunction "-_-") (pintype "passive"))
      (node (ref "R50") (pin "2") (pinfunction "2_2") (pintype "passive"))
    )
    (net (code "28") (name "Net-(C36-Pad+)") (class "Default")
      (node (ref "C36") (pin "+") (pinfunction "+_+") (pintype "passive"))
      (node (ref "R55") (pin "2") (pinfunction "2_2") (pintype "passive"))
    )
    (net (code "29") (name "Net-(C39-Pad+)") (class "Default")
      (node (ref "C39") (pin "+") (pinfunction "+_+") (pintype "passive"))
      (node (ref "R29") (pin "2") (pinfunction "2_2") (pintype "passive"))
    )
    (net (code "30") (name "Net-(C40-Pad1)") (class "Default")
      (node (ref "C40") (pin "1") (pinfunction "1_1") (pintype "passive"))
      (node (ref "D14") (pin "C") (pinfunction "C_C") (pintype "passive"))
      (node (ref "R69") (pin "1") (pinfunction "1_1") (pintype "passive"))
    )
    (net (code "31") (name "Net-(C41-Pad2)") (class "Default")
      (node (ref "C41") (pin "2") (pinfunction "2_2") (pintype "passive"))
      (node (ref "C42") (pin "2") (pinfunction "2_2") (pintype "passive"))
      (node (ref "C50") (pin "1") (pinfunction "1_1") (pintype "passive"))
      (node (ref "R71") (pin "1") (pinfunction "1_1") (pintype "passive"))
      (node (ref "R87") (pin "2") (pinfunction "2_2") (pintype "passive"))
      (node (ref "R90") (pin "2") (pinfunction "2_2") (pintype "passive"))
    )
    (net (code "32") (name "Net-(C47-Pad1)") (class "Default")
      (node (ref "C47") (pin "1") (pinfunction "1_1") (pintype "passive"))
      (node (ref "D13") (pin "C") (pinfunction "C_C") (pintype "passive"))
      (node (ref "R70") (pin "2") (pinfunction "2_2") (pintype "passive"))
    )
    (net (code "33") (name "Net-(D12-PadC)") (class "Default")
      (node (ref "D12") (pin "C") (pinfunction "C_C") (pintype "passive"))
      (node (ref "R79") (pin "1") (pinfunction "1_1") (pintype "passive"))
    )
    (net (code "34") (name "Net-(Q1-D)") (class "Default")
      (node (ref "Q1") (pin "3") (pinfunction "D_3") (pintype "passive"))
      (node (ref "SW1") (pin "P$1") (pinfunction "A_P$1") (pintype "bidirectional"))
    )
    (net (code "35") (name "Net-(Q1-G)") (class "Default")
      (node (ref "D13") (pin "A") (pinfunction "A_A") (pintype "passive"))
      (node (ref "Q1") (pin "1") (pinfunction "G_1") (pintype "passive"))
    )
    (net (code "36") (name "Net-(Q1-S)") (class "Default")
      (node (ref "C35") (pin "2") (pinfunction "2_2") (pintype "passive"))
      (node (ref "Q1") (pin "2") (pinfunction "S_2") (pintype "passive"))
      (node (ref "Q6") (pin "2") (pinfunction "S_2") (pintype "passive"))
      (node (ref "R75") (pin "2") (pinfunction "2_2") (pintype "passive"))
    )
    (net (code "37") (name "Net-(Q2-D)") (class "Default")
      (node (ref "Q2") (pin "3") (pinfunction "D_3") (pintype "passive"))
      (node (ref "R76") (pin "1") (pinfunction "1_1") (pintype "passive"))
      (node (ref "R79") (pin "2") (pinfunction "2_2") (pintype "passive"))
    )
    (net (code "38") (name "Net-(Q2-G)") (class "Default")
      (node (ref "C17") (pin "1") (pinfunction "1_1") (pintype "passive"))
      (node (ref "C7") (pin "1") (pinfunction "1_1") (pintype "passive"))
      (node (ref "D10") (pin "A") (pinfunction "A_A") (pintype "passive"))
      (node (ref "Q2") (pin "1") (pinfunction "G_1") (pintype "passive"))
      (node (ref "Q3") (pin "1") (pinfunction "G_1") (pintype "passive"))
      (node (ref "R86") (pin "2") (pinfunction "2_2") (pintype "passive"))
    )
    (net (code "39") (name "Net-(Q3-D)") (class "Default")
      (node (ref "C46") (pin "1") (pinfunction "1_1") (pintype "passive"))
      (node (ref "Q3") (pin "3") (pinfunction "D_3") (pintype "passive"))
      (node (ref "R77") (pin "1") (pinfunction "1_1") (pintype "passive"))
    )
    (net (code "40") (name "Net-(Q4-D)") (class "Default")
      (node (ref "Q4") (pin "3") (pinfunction "D_3") (pintype "passive"))
      (node (ref "SW1") (pin "P$4") (pinfunction "3_P$4") (pintype "bidirectional"))
      (node (ref "VR4") (pin "2") (pinfunction "2_2") (pintype "passive"))
    )
    (net (code "41") (name "Net-(Q4-G)") (class "Default")
      (node (ref "D12") (pin "A") (pinfunction "A_A") (pintype "passive"))
      (node (ref "Q4") (pin "1") (pinfunction "G_1") (pintype "passive"))
    )
    (net (code "42") (name "Net-(Q4-S)") (class "Default")
      (node (ref "C46") (pin "2") (pinfunction "2_2") (pintype "passive"))
      (node (ref "Q4") (pin "2") (pinfunction "S_2") (pintype "passive"))
      (node (ref "R78") (pin "1") (pinfunction "1_1") (pintype "passive"))
      (node (ref "SW1") (pin "P$2") (pinfunction "1_P$2") (pintype "bidirectional"))
      (node (ref "SW1") (pin "P$3") (pinfunction "2_P$3") (pintype "bidirectional"))
    )
    (net (code "43") (name "Net-(Q6-D)") (class "Default")
      (node (ref "C44") (pin "1") (pinfunction "1_1") (pintype "passive"))
      (node (ref "Q6") (pin "3") (pinfunction "D_3") (pintype "passive"))
      (node (ref "R65") (pin "2") (pinfunction "2_2") (pintype "passive"))
    )
    (net (code "44") (name "Net-(Q6-G)") (class "Default")
      (node (ref "D14") (pin "A") (pinfunction "A_A") (pintype "passive"))
      (node (ref "Q6") (pin "1") (pinfunction "G_1") (pintype "passive"))
    )
    (net (code "45") (name "Net-(R27-Pad2)") (class "Default")
      (node (ref "R27") (pin "2") (pinfunction "2_2") (pintype "passive"))
      (node (ref "VR1") (pin "1") (pinfunction "1_1") (pintype "passive"))
    )
    (net (code "46") (name "Net-(R49-Pad2)") (class "Default")
      (node (ref "R49") (pin "2") (pinfunction "2_2") (pintype "passive"))
      (node (ref "VR4") (pin "1") (pinfunction "1_1") (pintype "passive"))
    )
    (net (code "47") (name "Net-(SW2-1)") (class "Default")
      (node (ref "R8") (pin "2") (pinfunction "2_2") (pintype "passive"))
      (node (ref "SW2") (pin "P$2") (pinfunction "1_P$2") (pintype "bidirectional"))
    )
    (net (code "48") (name "Net-(SW2-2)") (class "Default")
      (node (ref "R7") (pin "2") (pinfunction "2_2") (pintype "passive"))
      (node (ref "R8") (pin "1") (pinfunction "1_1") (pintype "passive"))
      (node (ref "SW2") (pin "P$3") (pinfunction "2_P$3") (pintype "bidirectional"))
    )
    (net (code "49") (name "Net-(SW2-A)") (class "Default")
      (node (ref "R9") (pin "1") (pinfunction "1_1") (pintype "passive"))
      (node (ref "SW2") (pin "P$1") (pinfunction "A_P$1") (pintype "bidirectional"))
      (node (ref "U1") (pin "6") (pinfunction "-IN_6") (pintype "input"))
    )
    (net (code "50") (name "Net-(SW3-P)") (class "Default")
      (node (ref "R90") (pin "1") (pinfunction "1_1") (pintype "passive"))
      (node (ref "SW3") (pin "1") (pinfunction "P_1") (pintype "passive"))
    )
    (net (code "51") (name "Net-(SW4B-1)") (class "Default")
      (node (ref "C28") (pin "1") (pinfunction "1_1") (pintype "passive"))
      (node (ref "SW4") (pin "B1") (pinfunction "1_B1") (pintype "passive"))
    )
    (net (code "52") (name "Net-(SW4B-2)") (class "Default")
      (node (ref "R56") (pin "1") (pinfunction "1_1") (pintype "passive"))
      (node (ref "R57") (pin "1") (pinfunction "1_1") (pintype "passive"))
      (node (ref "R61") (pin "2") (pinfunction "2_2") (pintype "passive"))
      (node (ref "SW4") (pin "B2") (pinfunction "2_B2") (pintype "passive"))
      (node (ref "U2") (pin "3") (pinfunction "+IN_3") (pintype "input"))
      (node (ref "VR2") (pin "3") (pinfunction "3_3") (pintype "passive"))
      (node (ref "VR3") (pin "3") (pinfunction "3_3") (pintype "passive"))
    )
    (net (code "53") (name "Net-(TR1-B)") (class "Default")
      (node (ref "R1") (pin "2") (pinfunction "2_2") (pintype "passive"))
      (node (ref "R4") (pin "2") (pinfunction "2_2") (pintype "passive"))
      (node (ref "TR1") (pin "1") (pinfunction "B_1") (pintype "passive"))
    )
    (net (code "54") (name "Net-(TR1-E)") (class "Default")
      (node (ref "C3") (pin "2") (pinfunction "2_2") (pintype "passive"))
      (node (ref "R5") (pin "2") (pinfunction "2_2") (pintype "passive"))
      (node (ref "TR1") (pin "3") (pinfunction "E_3") (pintype "passive"))
      (node (ref "TR2") (pin "1") (pinfunction "B_1") (pintype "passive"))
    )
    (net (code "55") (name "Net-(TR2-E)") (class "Default")
      (node (ref "C44") (pin "2") (pinfunction "2_2") (pintype "passive"))
      (node (ref "R13") (pin "2") (pinfunction "2_2") (pintype "passive"))
      (node (ref "TR2") (pin "3") (pinfunction "E_3") (pintype "passive"))
    )
    (net (code "56") (name "Net-(TR3-B)") (class "Default")
      (node (ref "C10") (pin "2") (pinfunction "2_2") (pintype "passive"))
      (node (ref "R18") (pin "2") (pinfunction "2_2") (pintype "passive"))
      (node (ref "TR3") (pin "1") (pinfunction "B_1") (pintype "passive"))
    )
    (net (code "57") (name "Net-(TR3-E)") (class "Default")
      (node (ref "R17") (pin "2") (pinfunction "2_2") (pintype "passive"))
      (node (ref "R19") (pin "2") (pinfunction "2_2") (pintype "passive"))
      (node (ref "TR3") (pin "3") (pinfunction "E_3") (pintype "passive"))
    )
    (net (code "58") (name "Net-(TR4-B)") (class "Default")
      (node (ref "C12") (pin "2") (pinfunction "2_2") (pintype "passive"))
      (node (ref "R20") (pin "2") (pinfunction "2_2") (pintype "passive"))
      (node (ref "R21") (pin "1") (pinfunction "1_1") (pintype "passive"))
      (node (ref "R22") (pin "2") (pinfunction "2_2") (pintype "passive"))
      (node (ref "TR4") (pin "1") (pinfunction "B_1") (pintype "passive"))
    )
    (net (code "59") (name "Net-(TR4-C)") (class "Default")
      (node (ref "C12") (pin "1") (pinfunction "1_1") (pintype "passive"))
      (node (ref "C14") (pin "2") (pinfunction "2_2") (pintype "passive"))
      (node (ref "C4") (pin "2") (pinfunction "2_2") (pintype "passive"))
      (node (ref "R21") (pin "2") (pinfunction "2_2") (pintype "passive"))
      (node (ref "R23") (pin "1") (pinfunction "1_1") (pintype "passive"))
      (node (ref "TR4") (pin "2") (pinfunction "C_2") (pintype "passive"))
    )
    (net (code "60") (name "Net-(TR4-E)") (class "Default")
      (node (ref "R24") (pin "2") (pinfunction "2_2") (pintype "passive"))
      (node (ref "TR4") (pin "3") (pinfunction "E_3") (pintype "passive"))
    )
    (net (code "61") (name "Net-(TR5-B)") (class "Default")
      (node (ref "C21") (pin "2") (pinfunction "2_2") (pintype "passive"))
      (node (ref "R33") (pin "2") (pinfunction "2_2") (pintype "passive"))
      (node (ref "TR5") (pin "1") (pinfunction "B_1") (pintype "passive"))
    )
    (net (code "62") (name "Net-(TR5-E)") (class "Default")
      (node (ref "R32") (pin "2") (pinfunction "2_2") (pintype "passive"))
      (node (ref "R34") (pin "2") (pinfunction "2_2") (pintype "passive"))
      (node (ref "TR5") (pin "3") (pinfunction "E_3") (pintype "passive"))
    )
    (net (code "63") (name "Net-(TR6-B)") (class "Default")
      (node (ref "C23") (pin "2") (pinfunction "2_2") (pintype "passive"))
      (node (ref "R36") (pin "2") (pinfunction "2_2") (pintype "passive"))
      (node (ref "TR6") (pin "1") (pinfunction "B_1") (pintype "passive"))
    )
    (net (code "64") (name "Net-(TR6-E)") (class "Default")
      (node (ref "R35") (pin "2") (pinfunction "2_2") (pintype "passive"))
      (node (ref "R37") (pin "2") (pinfunction "2_2") (pintype "passive"))
      (node (ref "TR6") (pin "3") (pinfunction "E_3") (pintype "passive"))
    )
    (net (code "65") (name "Net-(TR7-B)") (class "Default")
      (node (ref "C25") (pin "2") (pinfunction "2_2") (pintype "passive"))
      (node (ref "R39") (pin "2") (pinfunction "2_2") (pintype "passive"))
      (node (ref "TR7") (pin "1") (pinfunction "B_1") (pintype "passive"))
    )
    (net (code "66") (name "Net-(TR7-E)") (class "Default")
      (node (ref "R38") (pin "2") (pinfunction "2_2") (pintype "passive"))
      (node (ref "R40") (pin "2") (pinfunction "2_2") (pintype "passive"))
      (node (ref "TR7") (pin "3") (pinfunction "E_3") (pintype "passive"))
    )
    (net (code "67") (name "Net-(TR8-B)") (class "Default")
      (node (ref "C27") (pin "2") (pinfunction "2_2") (pintype "passive"))
      (node (ref "R42") (pin "2") (pinfunction "2_2") (pintype "passive"))
      (node (ref "TR8") (pin "1") (pinfunction "B_1") (pintype "passive"))
    )
    (net (code "68") (name "Net-(TR8-E)") (class "Default")
      (node (ref "R41") (pin "2") (pinfunction "2_2") (pintype "passive"))
      (node (ref "R43") (pin "2") (pinfunction "2_2") (pintype "passive"))
      (node (ref "TR8") (pin "3") (pinfunction "E_3") (pintype "passive"))
    )
    (net (code "69") (name "Net-(TR9-B)") (class "Default")
      (node (ref "C29") (pin "2") (pinfunction "2_2") (pintype "passive"))
      (node (ref "R45") (pin "2") (pinfunction "2_2") (pintype "passive"))
      (node (ref "TR9") (pin "1") (pinfunction "B_1") (pintype "passive"))
    )
    (net (code "70") (name "Net-(TR9-E)") (class "Default")
      (node (ref "R44") (pin "2") (pinfunction "2_2") (pintype "passive"))
      (node (ref "R46") (pin "2") (pinfunction "2_2") (pintype "passive"))
      (node (ref "TR9") (pin "3") (pinfunction "E_3") (pintype "passive"))
    )
    (net (code "71") (name "Net-(TR10-B)") (class "Default")
      (node (ref "C35") (pin "1") (pinfunction "1_1") (pintype "passive"))
      (node (ref "R53") (pin "2") (pinfunction "2_2") (pintype "passive"))
      (node (ref "TR10") (pin "1") (pinfunction "B_1") (pintype "passive"))
    )
    (net (code "72") (name "Net-(TR10-E)") (class "Default")
      (node (ref "R54") (pin "2") (pinfunction "2_2") (pintype "passive"))
      (node (ref "R55") (pin "1") (pinfunction "1_1") (pintype "passive"))
      (node (ref "TR10") (pin "3") (pinfunction "E_3") (pintype "passive"))
    )
    (net (code "73") (name "Net-(TR11-B)") (class "Default")
      (node (ref "C41") (pin "1") (pinfunction "1_1") (pintype "passive"))
      (node (ref "C49") (pin "2") (pinfunction "2_2") (pintype "passive"))
      (node (ref "R80") (pin "1") (pinfunction "1_1") (pintype "passive"))
      (node (ref "R89") (pin "2") (pinfunction "2_2") (pintype "passive"))
      (node (ref "TR11") (pin "1") (pinfunction "B_1") (pintype "passive"))
    )
    (net (code "74") (name "Net-(TR11-C)") (class "Default")
      (node (ref "C48") (pin "2") (pinfunction "2_2") (pintype "passive"))
      (node (ref "R68") (pin "1") (pinfunction "1_1") (pintype "passive"))
      (node (ref "R69") (pin "2") (pinfunction "2_2") (pintype "passive"))
      (node (ref "R73") (pin "1") (pinfunction "1_1") (pintype "passive"))
      (node (ref "TR11") (pin "2") (pinfunction "C_2") (pintype "passive"))
    )
    (net (code "75") (name "Net-(TR12-B)") (class "Default")
      (node (ref "C42") (pin "1") (pinfunction "1_1") (pintype "passive"))
      (node (ref "C48") (pin "1") (pinfunction "1_1") (pintype "passive"))
      (node (ref "R73") (pin "2") (pinfunction "2_2") (pintype "passive"))
      (node (ref "R74") (pin "2") (pinfunction "2_2") (pintype "passive"))
      (node (ref "TR12") (pin "1") (pinfunction "B_1") (pintype "passive"))
    )
    (net (code "76") (name "Net-(TR12-C)") (class "Default")
      (node (ref "C49") (pin "1") (pinfunction "1_1") (pintype "passive"))
      (node (ref "R70") (pin "1") (pinfunction "1_1") (pintype "passive"))
      (node (ref "R80") (pin "2") (pinfunction "2_2") (pintype "passive"))
      (node (ref "R88") (pin "1") (pinfunction "1_1") (pintype "passive"))
      (node (ref "TR12") (pin "2") (pinfunction "C_2") (pintype "passive"))
    )
    (net (code "77") (name "Net-(U1A-+IN)") (class "Default")
      (node (ref "R14") (pin "2") (pinfunction "2_2") (pintype "passive"))
      (node (ref "U1") (pin "3") (pinfunction "+IN_3") (pintype "input"))
    )
    (net (code "78") (name "Net-(U1A--IN)") (class "Default")
      (node (ref "C8") (pin "2") (pinfunction "2_2") (pintype "passive"))
      (node (ref "C9") (pin "+") (pinfunction "+_+") (pintype "passive"))
      (node (ref "R15") (pin "1") (pinfunction "1_1") (pintype "passive"))
      (node (ref "U1") (pin "2") (pinfunction "-IN_2") (pintype "input"))
    )
    (net (code "79") (name "Net-(U1A-OUT)") (class "Default")
      (node (ref "C11") (pin "2") (pinfunction "2_2") (pintype "passive"))
      (node (ref "C8") (pin "1") (pinfunction "1_1") (pintype "passive"))
      (node (ref "R15") (pin "2") (pinfunction "2_2") (pintype "passive"))
      (node (ref "U1") (pin "1") (pinfunction "OUT_1") (pintype "output"))
    )
    (net (code "80") (name "Net-(U1B-+IN)") (class "Default")
      (node (ref "R12") (pin "2") (pinfunction "2_2") (pintype "passive"))
      (node (ref "U1") (pin "5") (pinfunction "+IN_5") (pintype "input"))
    )
    (net (code "81") (name "Net-(U1B-OUT)") (class "Default")
      (node (ref "C6") (pin "2") (pinfunction "2_2") (pintype "passive"))
      (node (ref "R9") (pin "2") (pinfunction "2_2") (pintype "passive"))
      (node (ref "U1") (pin "7") (pinfunction "OUT_7") (pintype "output"))
    )
    (net (code "82") (name "Net-(U2A--IN)") (class "Default")
      (node (ref "C30") (pin "2") (pinfunction "2_2") (pintype "passive"))
      (node (ref "R47") (pin "1") (pinfunction "1_1") (pintype "passive"))
      (node (ref "R48") (pin "2") (pinfunction "2_2") (pintype "passive"))
      (node (ref "R51") (pin "2") (pinfunction "2_2") (pintype "passive"))
      (node (ref "R52") (pin "2") (pinfunction "2_2") (pintype "passive"))
      (node (ref "U2") (pin "2") (pinfunction "-IN_2") (pintype "input"))
      (node (ref "VR2") (pin "1") (pinfunction "1_1") (pintype "passive"))
      (node (ref "VR3") (pin "1") (pinfunction "1_1") (pintype "passive"))
    )
    (net (code "83") (name "Net-(U2A-OUT)") (class "Default")
      (node (ref "C30") (pin "1") (pinfunction "1_1") (pintype "passive"))
      (node (ref "C32") (pin "+") (pinfunction "+_+") (pintype "passive"))
      (node (ref "R47") (pin "2") (pinfunction "2_2") (pintype "passive"))
      (node (ref "U2") (pin "1") (pinfunction "OUT_1") (pintype "output"))
    )
    (net (code "84") (name "Net-(U2B-+IN)") (class "Default")
      (node (ref "R25") (pin "2") (pinfunction "2_2") (pintype "passive"))
      (node (ref "R26") (pin "2") (pinfunction "2_2") (pintype "passive"))
      (node (ref "U2") (pin "5") (pinfunction "+IN_5") (pintype "input"))
    )
    (net (code "85") (name "Net-(U2B--IN)") (class "Default")
      (node (ref "C18") (pin "2") (pinfunction "2_2") (pintype "passive"))
      (node (ref "D3") (pin "C") (pinfunction "C_C") (pintype "passive"))
      (node (ref "D4") (pin "A") (pinfunction "A_A") (pintype "passive"))
      (node (ref "R27") (pin "1") (pinfunction "1_1") (pintype "passive"))
      (node (ref "R91") (pin "2") (pinfunction "2_2") (pintype "passive"))
      (node (ref "U2") (pin "6") (pinfunction "-IN_6") (pintype "input"))
    )
    (net (code "86") (name "Net-(U2B-OUT)") (class "Default")
      (node (ref "C18") (pin "1") (pinfunction "1_1") (pintype "passive"))
      (node (ref "D3") (pin "A") (pinfunction "A_A") (pintype "passive"))
      (node (ref "D4") (pin "C") (pinfunction "C_C") (pintype "passive"))
      (node (ref "R29") (pin "1") (pinfunction "1_1") (pintype "passive"))
      (node (ref "U2") (pin "7") (pinfunction "OUT_7") (pintype "output"))
      (node (ref "VR1") (pin "2") (pinfunction "2_2") (pintype "passive"))
      (node (ref "VR1") (pin "3") (pinfunction "3_3") (pintype "passive"))
    )
    (net (code "87") (name "OUT") (class "Default")
      (node (ref "C36") (pin "-") (pinfunction "-_-") (pintype "passive"))
      (node (ref "R58") (pin "2") (pinfunction "2_2") (pintype "passive"))
    )
    (net (code "88") (name "VB") (class "Default")
      (node (ref "C38") (pin "+") (pinfunction "+_+") (pintype "passive"))
      (node (ref "R18") (pin "1") (pinfunction "1_1") (pintype "passive"))
      (node (ref "R22") (pin "1") (pinfunction "1_1") (pintype "passive"))
      (node (ref "R24") (pin "1") (pinfunction "1_1") (pintype "passive"))
      (node (ref "R26") (pin "1") (pinfunction "1_1") (pintype "passive"))
      (node (ref "R31") (pin "1") (pinfunction "1_1") (pintype "passive"))
      (node (ref "R33") (pin "1") (pinfunction "1_1") (pintype "passive"))
      (node (ref "R36") (pin "1") (pinfunction "1_1") (pintype "passive"))
      (node (ref "R39") (pin "1") (pinfunction "1_1") (pintype "passive"))
      (node (ref "R42") (pin "1") (pinfunction "1_1") (pintype "passive"))
      (node (ref "R45") (pin "1") (pinfunction "1_1") (pintype "passive"))
      (node (ref "R53") (pin "1") (pinfunction "1_1") (pintype "passive"))
      (node (ref "R59") (pin "2") (pinfunction "2_2") (pintype "passive"))
      (node (ref "R6") (pin "1") (pinfunction "1_1") (pintype "passive"))
      (node (ref "R60") (pin "2") (pinfunction "2_2") (pintype "passive"))
      (node (ref "R65") (pin "1") (pinfunction "1_1") (pintype "passive"))
      (node (ref "R75") (pin "1") (pinfunction "1_1") (pintype "passive"))
      (node (ref "R78") (pin "2") (pinfunction "2_2") (pintype "passive"))
      (node (ref "SW2") (pin "P$4") (pinfunction "3_P$4") (pintype "bidirectional"))
      (node (ref "VR4") (pin "3") (pinfunction "3_3") (pintype "passive"))
    )
    (net (code "89") (name "unconnected-(SW4A-1-PadA1)") (class "Default")
      (node (ref "SW4") (pin "A1") (pinfunction "1_A1") (pintype "passive"))
    )
    (net (code "90") (name "unconnected-(SW4A-3-PadA3)") (class "Default")
      (node (ref "SW4") (pin "A3") (pinfunction "3_A3") (pintype "passive"))
    )
    (net (code "91") (name "unconnected-(SW4B-3-PadB3)") (class "Default")
      (node (ref "SW4") (pin "B3") (pinfunction "3_B3") (pintype "passive"))
    )
  )
)
